# CANBed_FD.net
KiCad netlist of a schematic drawn in EAGLE
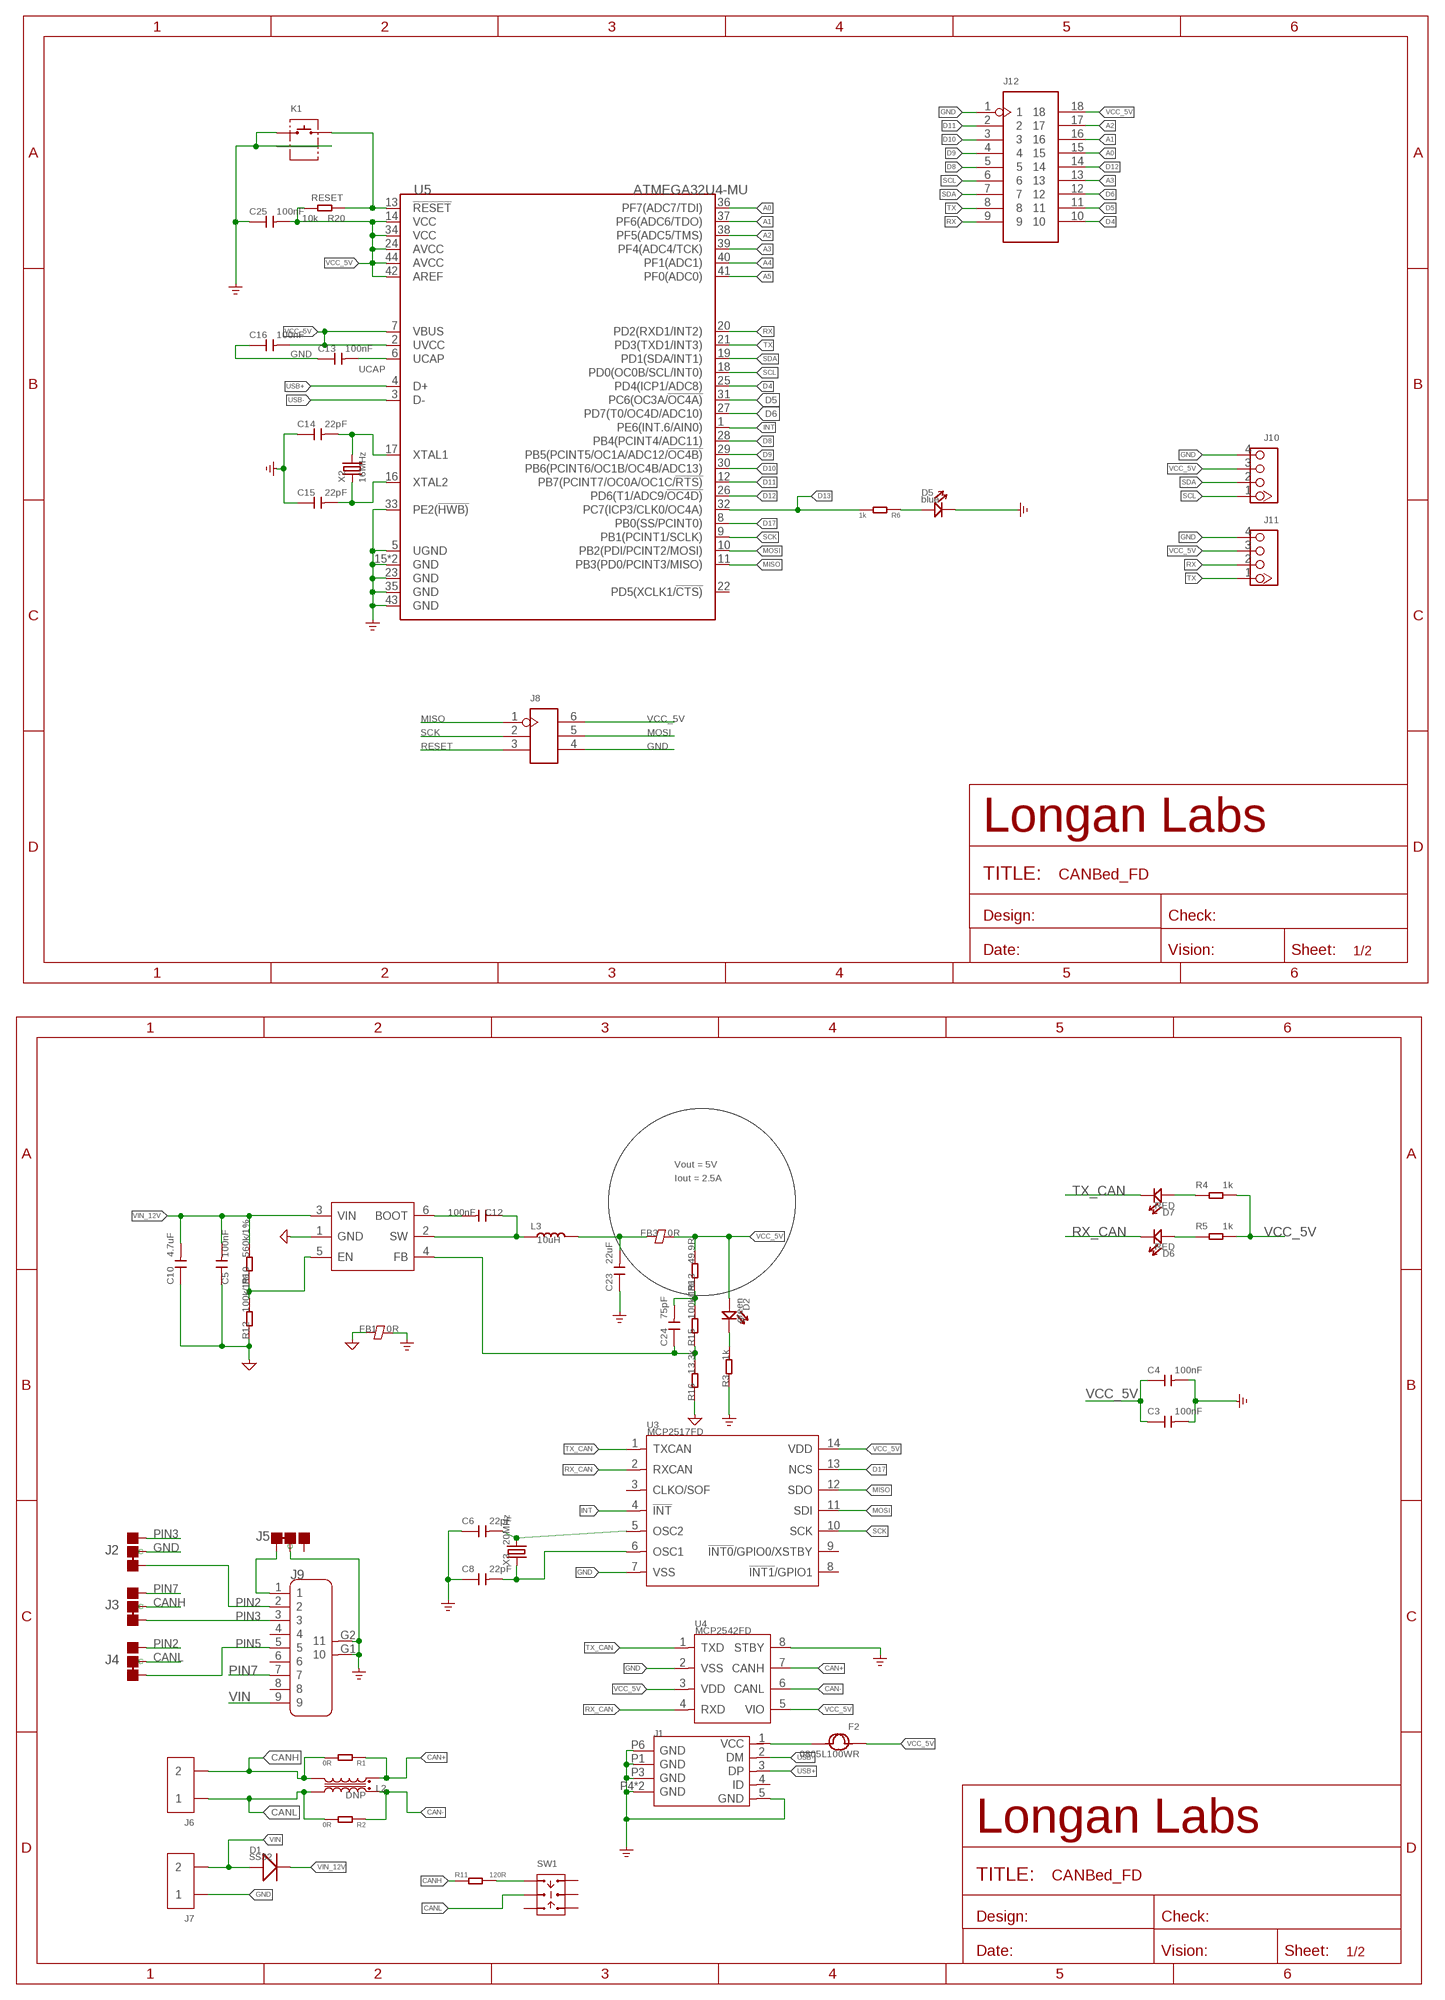
[diagram p0: schematic, sheet 1]

(export (version "E")
  (design (tool "Eeschema 10.0.6"))
  (components
    (comp (ref "C3")
      (value "100nF")
      (footprint "eagle-import:C0603")
      (libsource (lib "eagle-import") (part "CAP-0603"))
    )
    (comp (ref "C4")
      (value "100nF")
      (footprint "eagle-import:C0603")
      (libsource (lib "eagle-import") (part "CAP-0603"))
    )
    (comp (ref "C5")
      (value "100nF")
      (footprint "eagle-import:C0603")
      (libsource (lib "eagle-import") (part "CAP-0603"))
    )
    (comp (ref "C6")
      (value "22pF")
      (footprint "eagle-import:C0603")
      (libsource (lib "eagle-import") (part "CAP-0603"))
    )
    (comp (ref "C8")
      (value "22pF")
      (footprint "eagle-import:C0603")
      (libsource (lib "eagle-import") (part "CAP-0603"))
    )
    (comp (ref "C10")
      (value "4.7uF")
      (footprint "eagle-import:C1206")
      (libsource (lib "eagle-import") (part "CAP-1206"))
    )
    (comp (ref "C12")
      (value "100nF")
      (footprint "eagle-import:C0603")
      (libsource (lib "eagle-import") (part "CAP-0603"))
    )
    (comp (ref "C13")
      (value "100nF")
      (footprint "eagle-import:C0603")
      (libsource (lib "eagle-import") (part "CAP-0603"))
    )
    (comp (ref "C14")
      (value "22pF")
      (footprint "eagle-import:C0603")
      (libsource (lib "eagle-import") (part "CAP-0603"))
    )
    (comp (ref "C15")
      (value "22pF")
      (footprint "eagle-import:C0603")
      (libsource (lib "eagle-import") (part "CAP-0603"))
    )
    (comp (ref "C16")
      (value "100nF")
      (footprint "eagle-import:C0603")
      (libsource (lib "eagle-import") (part "CAP-0603"))
    )
    (comp (ref "C23")
      (value "22uF")
      (footprint "eagle-import:C1206")
      (libsource (lib "eagle-import") (part "CAP-1206"))
    )
    (comp (ref "C24")
      (value "75pF")
      (footprint "eagle-import:C0603")
      (libsource (lib "eagle-import") (part "CAP-0603"))
    )
    (comp (ref "C25")
      (value "100nF")
      (footprint "eagle-import:C0603")
      (libsource (lib "eagle-import") (part "CAP-0603"))
    )
    (comp (ref "D1")
      (value "SS32")
      (footprint "eagle-import:DO-214AC")
      (libsource (lib "eagle-import") (part "DIODE'SMA'"))
    )
    (comp (ref "D2")
      (value "green")
      (footprint "eagle-import:LED-0603")
      (libsource (lib "eagle-import") (part "LED'0603'"))
    )
    (comp (ref "D5")
      (value "blue")
      (footprint "eagle-import:LED-0603")
      (libsource (lib "eagle-import") (part "LED'0603'"))
    )
    (comp (ref "D6")
      (value "RED")
      (footprint "eagle-import:LED-0603")
      (libsource (lib "eagle-import") (part "LED'0603'"))
    )
    (comp (ref "D7")
      (value "RED")
      (footprint "eagle-import:LED-0603")
      (libsource (lib "eagle-import") (part "LED'0603'"))
    )
    (comp (ref "F2")
      (value "0805L100WR")
      (footprint "eagle-import:F0805")
      (libsource (lib "eagle-import") (part "FUSE0805"))
    )
    (comp (ref "FB1")
      (value "0R")
      (footprint "eagle-import:F0805")
      (libsource (lib "eagle-import") (part "FERRITE-BEAD-0805"))
    )
    (comp (ref "FB3")
      (value "0R")
      (footprint "eagle-import:F0805")
      (libsource (lib "eagle-import") (part "FERRITE-BEAD-0805"))
    )
    (comp (ref "J1")
      (value "MICRO-USB5+4P-320010050")
      (footprint "eagle-import:MICRO-USB5+5P-SMD-0.65-7.2X5.06MM")
      (libsource (lib "eagle-import") (part "MICRO-USB5+4P-320010050"))
    )
    (comp (ref "J2")
      (value "JUMPER-3P-SHORT")
      (footprint "eagle-import:3P-SMD-SHORT")
      (libsource (lib "eagle-import") (part "JUMPER-3P-SHORT"))
    )
    (comp (ref "J3")
      (value "JUMPER-3P-SHORT")
      (footprint "eagle-import:3P-SMD-SHORT")
      (libsource (lib "eagle-import") (part "JUMPER-3P-SHORT"))
    )
    (comp (ref "J4")
      (value "JUMPER-3P-SHORT")
      (footprint "eagle-import:3P-SMD-SHORT")
      (libsource (lib "eagle-import") (part "JUMPER-3P-SHORT"))
    )
    (comp (ref "J5")
      (value "JUMPER-3P-SHORT")
      (footprint "eagle-import:3P-SMD-SHORT")
      (libsource (lib "eagle-import") (part "JUMPER-3P-SHORT"))
    )
    (comp (ref "J6")
      (value "SCREW-TERMINAL-2P'5.08'")
      (footprint "eagle-import:H2-5.0-10.5X8.0MM")
      (libsource (lib "eagle-import") (part "SCREW-TERMINAL-2P'5.08'"))
    )
    (comp (ref "J7")
      (value "SCREW-TERMINAL-2P'5.08'")
      (footprint "eagle-import:H2-5.0-10.5X8.0MM")
      (libsource (lib "eagle-import") (part "SCREW-TERMINAL-2P'5.08'"))
    )
    (comp (ref "J8")
      (value "HEADER-2X3P-2.54")
      (footprint "eagle-import:H2X3-2.54")
      (libsource (lib "eagle-import") (part "HEADER-2X3P-2.54"))
    )
    (comp (ref "J9")
      (value "DB9'MEAL'")
      (footprint "eagle-import:DB9-MEAL")
      (libsource (lib "eagle-import") (part "DB9'MEAL'"))
    )
    (comp (ref "J10")
      (value "320110033")
      (footprint "eagle-import:HW4-2.0")
      (libsource (lib "eagle-import") (part "GROVE-CONNECTOR-DIP-2.0"))
    )
    (comp (ref "J11")
      (value "320110033")
      (footprint "eagle-import:HW4-2.0")
      (libsource (lib "eagle-import") (part "GROVE-CONNECTOR-DIP-2.0"))
    )
    (comp (ref "J12")
      (value "HEADER-2X9P-2.54")
      (footprint "eagle-import:H2X9-2.54")
      (libsource (lib "eagle-import") (part "HEADER-2X9P-2.54"))
    )
    (comp (ref "K1")
      (value "BUTTON-2+2P")
      (footprint "eagle-import:SW2+2P-7.7X2.75X3.95MM")
      (libsource (lib "eagle-import") (part "BUTTON-2+2P"))
    )
    (comp (ref "L2")
      (value "DNP")
      (footprint "eagle-import:INT4-0.85-2X1.25X1.2MM")
      (libsource (lib "eagle-import") (part "INDUCTOR-COMMON-MODE-SRF2012-900YA"))
    )
    (comp (ref "L3")
      (value "10uH")
      (footprint "eagle-import:INT2-SMD-6.6X7.1X3MM")
      (libsource (lib "eagle-import") (part "INDUCTOR-6.6X7.1"))
    )
    (comp (ref "R1")
      (value "0R")
      (footprint "eagle-import:R0603")
      (libsource (lib "eagle-import") (part "RES-0603"))
    )
    (comp (ref "R2")
      (value "0R")
      (footprint "eagle-import:R0603")
      (libsource (lib "eagle-import") (part "RES-0603"))
    )
    (comp (ref "R3")
      (value "1k")
      (footprint "eagle-import:R0603")
      (libsource (lib "eagle-import") (part "RES-0603"))
    )
    (comp (ref "R4")
      (value "1k")
      (footprint "eagle-import:R0603")
      (libsource (lib "eagle-import") (part "RES-0603"))
    )
    (comp (ref "R5")
      (value "1k")
      (footprint "eagle-import:R0603")
      (libsource (lib "eagle-import") (part "RES-0603"))
    )
    (comp (ref "R6")
      (value "1k")
      (footprint "eagle-import:R0603")
      (libsource (lib "eagle-import") (part "RES-0603"))
    )
    (comp (ref "R10")
      (value "560k/1%")
      (footprint "eagle-import:R0603")
      (libsource (lib "eagle-import") (part "RES-0603"))
    )
    (comp (ref "R11")
      (value "120R")
      (footprint "eagle-import:R0603")
      (libsource (lib "eagle-import") (part "RES-0603"))
    )
    (comp (ref "R12")
      (value "100k/1%")
      (footprint "eagle-import:R0603")
      (libsource (lib "eagle-import") (part "RES-0603"))
    )
    (comp (ref "R13")
      (value "49.9R")
      (footprint "eagle-import:R0603")
      (libsource (lib "eagle-import") (part "RES-0603"))
    )
    (comp (ref "R15")
      (value "100k/1%")
      (footprint "eagle-import:R0603")
      (libsource (lib "eagle-import") (part "RES-0603"))
    )
    (comp (ref "R16")
      (value "13.3k")
      (footprint "eagle-import:R0603")
      (libsource (lib "eagle-import") (part "RES-0603"))
    )
    (comp (ref "R20")
      (value "10k")
      (footprint "eagle-import:R0603")
      (libsource (lib "eagle-import") (part "RES-0603"))
    )
    (comp (ref "SW1")
      (value "SWITCH-2CH-6P-311010004")
      (footprint "eagle-import:SW6-2.54-9.0X3.5X3.2+2.0MM")
      (libsource (lib "eagle-import") (part "SWITCH-2CH-6P-311010004"))
    )
    (comp (ref "U1")
      (value "PMIC-TPS54302")
      (footprint "eagle-import:SOT-23-6")
      (libsource (lib "eagle-import") (part "PMIC-TPS54302"))
    )
    (comp (ref "U3")
      (value "MCP2517FD")
      (footprint "eagle-import:SOIC14-1.27-8.6X3.9MM")
      (libsource (lib "eagle-import") (part "CONTROLLER-MCP2517FD"))
    )
    (comp (ref "U4")
      (value "MCP2542FD")
      (footprint "eagle-import:SOIC8-1.27-5X4MM")
      (libsource (lib "eagle-import") (part "TRANSCEIVER-MCP2542"))
    )
    (comp (ref "U5")
      (value "ATMEGA32U4-MU")
      (footprint "eagle-import:QFN44")
      (libsource (lib "eagle-import") (part "ATMEGA32U4-MU"))
    )
    (comp (ref "X2")
      (value "16MHz")
      (footprint "eagle-import:HC49US")
      (libsource (lib "eagle-import") (part "CRYSTAL-2P'HC49US'"))
    )
    (comp (ref "X3")
      (value "20MHz")
      (footprint "eagle-import:HC49US")
      (libsource (lib "eagle-import") (part "CRYSTAL-2P'HC49US'"))
    )
  )
  (nets
    (net (code "1") (name "A0") (class "Default")
      (node (ref "J12") (pin "15") (pinfunction "15_15") (pintype "bidirectional"))
      (node (ref "U5") (pin "36") (pinfunction "PF7(ADC7/TDI)_36") (pintype "bidirectional"))
    )
    (net (code "2") (name "A1") (class "Default")
      (node (ref "J12") (pin "16") (pinfunction "16_16") (pintype "bidirectional"))
      (node (ref "U5") (pin "37") (pinfunction "PF6(ADC6/TDO)_37") (pintype "bidirectional"))
    )
    (net (code "3") (name "A2") (class "Default")
      (node (ref "J12") (pin "17") (pinfunction "17_17") (pintype "bidirectional"))
      (node (ref "U5") (pin "38") (pinfunction "PF5(ADC5/TMS)_38") (pintype "bidirectional"))
    )
    (net (code "4") (name "A3") (class "Default")
      (node (ref "J12") (pin "13") (pinfunction "13_13") (pintype "bidirectional"))
      (node (ref "U5") (pin "39") (pinfunction "PF4(ADC4/TCK)_39") (pintype "bidirectional"))
    )
    (net (code "5") (name "A4") (class "Default")
      (node (ref "U5") (pin "40") (pinfunction "PF1(ADC1)_40") (pintype "bidirectional"))
    )
    (net (code "6") (name "A5") (class "Default")
      (node (ref "U5") (pin "41") (pinfunction "PF0(ADC0)_41") (pintype "bidirectional"))
    )
    (net (code "7") (name "AGND") (class "Default")
      (node (ref "C10") (pin "1") (pinfunction "1_1") (pintype "passive"))
      (node (ref "C5") (pin "1") (pinfunction "1_1") (pintype "passive"))
      (node (ref "FB1") (pin "1") (pinfunction "1_1") (pintype "bidirectional"))
      (node (ref "R12") (pin "1") (pinfunction "1_1") (pintype "passive"))
      (node (ref "R16") (pin "1") (pinfunction "1_1") (pintype "passive"))
      (node (ref "U1") (pin "1") (pinfunction "GND_1") (pintype "bidirectional"))
    )
    (net (code "8") (name "CAN+") (class "Default")
      (node (ref "L2") (pin "4") (pinfunction "4_4") (pintype "bidirectional"))
      (node (ref "R1") (pin "1") (pinfunction "1_1") (pintype "passive"))
      (node (ref "U4") (pin "7") (pinfunction "CANH_7") (pintype "bidirectional"))
    )
    (net (code "9") (name "CAN-") (class "Default")
      (node (ref "L2") (pin "1") (pinfunction "1_1") (pintype "bidirectional"))
      (node (ref "R2") (pin "1") (pinfunction "1_1") (pintype "passive"))
      (node (ref "U4") (pin "6") (pinfunction "CANL_6") (pintype "bidirectional"))
    )
    (net (code "10") (name "CANH") (class "Default")
      (node (ref "J3") (pin "MM") (pinfunction "C_MM") (pintype "bidirectional"))
      (node (ref "J6") (pin "2") (pinfunction "2_2") (pintype "bidirectional"))
      (node (ref "L2") (pin "3") (pinfunction "3_3") (pintype "bidirectional"))
      (node (ref "R1") (pin "2") (pinfunction "2_2") (pintype "passive"))
      (node (ref "R11") (pin "1") (pinfunction "1_1") (pintype "passive"))
    )
    (net (code "11") (name "CANL") (class "Default")
      (node (ref "J4") (pin "MM") (pinfunction "C_MM") (pintype "bidirectional"))
      (node (ref "J6") (pin "1") (pinfunction "1_1") (pintype "bidirectional"))
      (node (ref "L2") (pin "2") (pinfunction "2_2") (pintype "bidirectional"))
      (node (ref "R2") (pin "2") (pinfunction "2_2") (pintype "passive"))
      (node (ref "SW1") (pin "COM1") (pinfunction "COM1_COM1") (pintype "bidirectional"))
    )
    (net (code "12") (name "D4") (class "Default")
      (node (ref "J12") (pin "10") (pinfunction "10_10") (pintype "bidirectional"))
      (node (ref "U5") (pin "25") (pinfunction "PD4(ICP1/ADC8)_25") (pintype "bidirectional"))
    )
    (net (code "13") (name "D5") (class "Default")
      (node (ref "J12") (pin "11") (pinfunction "11_11") (pintype "bidirectional"))
      (node (ref "U5") (pin "31") (pinfunction "PC6(OC3A/~{OC4A})_31") (pintype "bidirectional"))
    )
    (net (code "14") (name "D6") (class "Default")
      (node (ref "J12") (pin "12") (pinfunction "12_12") (pintype "bidirectional"))
      (node (ref "U5") (pin "27") (pinfunction "PD7(T0/OC4D/ADC10)_27") (pintype "bidirectional"))
    )
    (net (code "15") (name "D8") (class "Default")
      (node (ref "J12") (pin "5") (pinfunction "5_5") (pintype "bidirectional"))
      (node (ref "U5") (pin "28") (pinfunction "PB4(PCINT4/ADC11)_28") (pintype "bidirectional"))
    )
    (net (code "16") (name "D9") (class "Default")
      (node (ref "J12") (pin "4") (pinfunction "4_4") (pintype "bidirectional"))
      (node (ref "U5") (pin "29") (pinfunction "PB5(PCINT5/OC1A/ADC12/~{OC4B})_29") (pintype "bidirectional"))
    )
    (net (code "17") (name "D10") (class "Default")
      (node (ref "J12") (pin "3") (pinfunction "3_3") (pintype "bidirectional"))
      (node (ref "U5") (pin "30") (pinfunction "PB6(PCINT6/OC1B/OC4B/ADC13)_30") (pintype "bidirectional"))
    )
    (net (code "18") (name "D11") (class "Default")
      (node (ref "J12") (pin "2") (pinfunction "2_2") (pintype "bidirectional"))
      (node (ref "U5") (pin "12") (pinfunction "PB7(PCINT7/OC0A/OC1C/~{RTS})_12") (pintype "bidirectional"))
    )
    (net (code "19") (name "D12") (class "Default")
      (node (ref "J12") (pin "14") (pinfunction "14_14") (pintype "bidirectional"))
      (node (ref "U5") (pin "26") (pinfunction "PD6(T1/ADC9/~{OC4D})_26") (pintype "bidirectional"))
    )
    (net (code "20") (name "D13") (class "Default")
      (node (ref "R6") (pin "2") (pinfunction "2_2") (pintype "passive"))
      (node (ref "U5") (pin "32") (pinfunction "PC7(ICP3/CLK0/OC4A)_32") (pintype "bidirectional"))
    )
    (net (code "21") (name "D17") (class "Default")
      (node (ref "U3") (pin "13") (pinfunction "NCS_13") (pintype "bidirectional"))
      (node (ref "U5") (pin "8") (pinfunction "PB0(SS/PCINT0)_8") (pintype "bidirectional"))
    )
    (net (code "22") (name "GND") (class "Default")
      (node (ref "C13") (pin "1") (pinfunction "1_1") (pintype "passive"))
      (node (ref "C14") (pin "1") (pinfunction "1_1") (pintype "passive"))
      (node (ref "C15") (pin "1") (pinfunction "1_1") (pintype "passive"))
      (node (ref "C16") (pin "1") (pinfunction "1_1") (pintype "passive"))
      (node (ref "C23") (pin "1") (pinfunction "1_1") (pintype "passive"))
      (node (ref "C25") (pin "1") (pinfunction "1_1") (pintype "passive"))
      (node (ref "C3") (pin "2") (pinfunction "2_2") (pintype "passive"))
      (node (ref "C4") (pin "2") (pinfunction "2_2") (pintype "passive"))
      (node (ref "C6") (pin "1") (pinfunction "1_1") (pintype "passive"))
      (node (ref "C8") (pin "1") (pinfunction "1_1") (pintype "passive"))
      (node (ref "D5") (pin "-") (pinfunction "-_-") (pintype "passive"))
      (node (ref "FB1") (pin "2") (pinfunction "2_2") (pintype "bidirectional"))
      (node (ref "J1") (pin "5") (pinfunction "GND_5") (pintype "bidirectional"))
      (node (ref "J1") (pin "P1") (pinfunction "GND_P1") (pintype "bidirectional"))
      (node (ref "J1") (pin "P3") (pinfunction "GND_P3") (pintype "bidirectional"))
      (node (ref "J1") (pin "P4") (pinfunction "GND_P4") (pintype "bidirectional"))
      (node (ref "J1") (pin "P5") (pinfunction "GND_P5") (pintype "bidirectional"))
      (node (ref "J1") (pin "P6") (pinfunction "GND_P6") (pintype "bidirectional"))
      (node (ref "J10") (pin "4") (pinfunction "4_4") (pintype "bidirectional"))
      (node (ref "J11") (pin "4") (pinfunction "4_4") (pintype "bidirectional"))
      (node (ref "J12") (pin "1") (pinfunction "1_1") (pintype "bidirectional"))
      (node (ref "J2") (pin "MM") (pinfunction "C_MM") (pintype "bidirectional"))
      (node (ref "J5") (pin "MM") (pinfunction "C_MM") (pintype "bidirectional"))
      (node (ref "J7") (pin "1") (pinfunction "1_1") (pintype "bidirectional"))
      (node (ref "J8") (pin "4") (pinfunction "4_4") (pintype "bidirectional"))
      (node (ref "J9") (pin "G1") (pinfunction "10_G1") (pintype "bidirectional"))
      (node (ref "J9") (pin "G2") (pinfunction "11_G2") (pintype "bidirectional"))
      (node (ref "K1") (pin "1") (pinfunction "1_1") (pintype "bidirectional"))
      (node (ref "K1") (pin "S1") (pinfunction "S1_S1") (pintype "bidirectional"))
      (node (ref "K1") (pin "S2") (pinfunction "S2_S2") (pintype "bidirectional"))
      (node (ref "R3") (pin "1") (pinfunction "1_1") (pintype "passive"))
      (node (ref "U3") (pin "7") (pinfunction "VSS_7") (pintype "bidirectional"))
      (node (ref "U4") (pin "2") (pinfunction "VSS_2") (pintype "bidirectional"))
      (node (ref "U4") (pin "8") (pinfunction "STBY_8") (pintype "bidirectional"))
      (node (ref "U5") (pin "15") (pinfunction "GND_15") (pintype "bidirectional"))
      (node (ref "U5") (pin "23") (pinfunction "GND_23") (pintype "bidirectional"))
      (node (ref "U5") (pin "33") (pinfunction "PE2(~{HWB})_33") (pintype "bidirectional"))
      (node (ref "U5") (pin "35") (pinfunction "GND_35") (pintype "bidirectional"))
      (node (ref "U5") (pin "43") (pinfunction "GND_43") (pintype "bidirectional"))
      (node (ref "U5") (pin "5") (pinfunction "UGND_5") (pintype "bidirectional"))
      (node (ref "U5") (pin "TAB") (pinfunction "GND_TAB") (pintype "bidirectional"))
    )
    (net (code "23") (name "INT") (class "Default")
      (node (ref "U3") (pin "4") (pinfunction "~{INT}_4") (pintype "bidirectional"))
      (node (ref "U5") (pin "1") (pinfunction "PE6(INT.6/AIN0)_1") (pintype "bidirectional"))
    )
    (net (code "24") (name "MISO") (class "Default")
      (node (ref "J8") (pin "1") (pinfunction "1_1") (pintype "bidirectional"))
      (node (ref "U3") (pin "12") (pinfunction "SDO_12") (pintype "bidirectional"))
      (node (ref "U5") (pin "11") (pinfunction "PB3(PD0/PCINT3/MISO)_11") (pintype "bidirectional"))
    )
    (net (code "25") (name "MOSI") (class "Default")
      (node (ref "J8") (pin "5") (pinfunction "5_5") (pintype "bidirectional"))
      (node (ref "U3") (pin "11") (pinfunction "SDI_11") (pintype "bidirectional"))
      (node (ref "U5") (pin "10") (pinfunction "PB2(PDI/PCINT2/MOSI)_10") (pintype "bidirectional"))
    )
    (net (code "26") (name "Net-(C23-Pad2)") (class "Default")
      (node (ref "C23") (pin "2") (pinfunction "2_2") (pintype "passive"))
      (node (ref "FB3") (pin "1") (pinfunction "1_1") (pintype "bidirectional"))
      (node (ref "L3") (pin "2") (pinfunction "2_2") (pintype "passive"))
    )
    (net (code "27") (name "Net-(C24-Pad2)") (class "Default")
      (node (ref "C24") (pin "2") (pinfunction "2_2") (pintype "passive"))
      (node (ref "R13") (pin "1") (pinfunction "1_1") (pintype "passive"))
      (node (ref "R15") (pin "2") (pinfunction "2_2") (pintype "passive"))
    )
    (net (code "28") (name "Net-(D2-Pad-)") (class "Default")
      (node (ref "D2") (pin "-") (pinfunction "-_-") (pintype "passive"))
      (node (ref "R3") (pin "2") (pinfunction "2_2") (pintype "passive"))
    )
    (net (code "29") (name "Net-(D5-Pad+)") (class "Default")
      (node (ref "D5") (pin "+") (pinfunction "+_+") (pintype "passive"))
      (node (ref "R6") (pin "1") (pinfunction "1_1") (pintype "passive"))
    )
    (net (code "30") (name "Net-(D6-Pad+)") (class "Default")
      (node (ref "D6") (pin "+") (pinfunction "+_+") (pintype "passive"))
      (node (ref "R5") (pin "1") (pinfunction "1_1") (pintype "passive"))
    )
    (net (code "31") (name "Net-(D7-Pad+)") (class "Default")
      (node (ref "D7") (pin "+") (pinfunction "+_+") (pintype "passive"))
      (node (ref "R4") (pin "1") (pinfunction "1_1") (pintype "passive"))
    )
    (net (code "32") (name "Net-(J1-VCC)") (class "Default")
      (node (ref "F2") (pin "2") (pinfunction "2_2") (pintype "bidirectional"))
      (node (ref "J1") (pin "1") (pinfunction "VCC_1") (pintype "bidirectional"))
    )
    (net (code "33") (name "Net-(J5-L)") (class "Default")
      (node (ref "J5") (pin "11") (pinfunction "L_11") (pintype "bidirectional"))
      (node (ref "J9") (pin "1") (pinfunction "1_1") (pintype "bidirectional"))
    )
    (net (code "34") (name "Net-(R11-Pad2)") (class "Default")
      (node (ref "R11") (pin "2") (pinfunction "2_2") (pintype "passive"))
      (node (ref "SW1") (pin "CH1A") (pinfunction "CH1A_CH1A") (pintype "bidirectional"))
    )
    (net (code "35") (name "Net-(U1-BOOT)") (class "Default")
      (node (ref "C12") (pin "2") (pinfunction "2_2") (pintype "passive"))
      (node (ref "U1") (pin "6") (pinfunction "BOOT_6") (pintype "bidirectional"))
    )
    (net (code "36") (name "Net-(U1-EN)") (class "Default")
      (node (ref "R10") (pin "1") (pinfunction "1_1") (pintype "passive"))
      (node (ref "R12") (pin "2") (pinfunction "2_2") (pintype "passive"))
      (node (ref "U1") (pin "5") (pinfunction "EN_5") (pintype "bidirectional"))
    )
    (net (code "37") (name "Net-(U1-FB)") (class "Default")
      (node (ref "C24") (pin "1") (pinfunction "1_1") (pintype "passive"))
      (node (ref "R15") (pin "1") (pinfunction "1_1") (pintype "passive"))
      (node (ref "R16") (pin "2") (pinfunction "2_2") (pintype "passive"))
      (node (ref "U1") (pin "4") (pinfunction "FB_4") (pintype "bidirectional"))
    )
    (net (code "38") (name "Net-(U1-SW)") (class "Default")
      (node (ref "C12") (pin "1") (pinfunction "1_1") (pintype "passive"))
      (node (ref "L3") (pin "1") (pinfunction "1_1") (pintype "passive"))
      (node (ref "U1") (pin "2") (pinfunction "SW_2") (pintype "bidirectional"))
    )
    (net (code "39") (name "Net-(U3-OSC1)") (class "Default")
      (node (ref "C8") (pin "2") (pinfunction "2_2") (pintype "passive"))
      (node (ref "U3") (pin "6") (pinfunction "OSC1_6") (pintype "bidirectional"))
      (node (ref "X3") (pin "1") (pinfunction "1_1") (pintype "passive"))
    )
    (net (code "40") (name "Net-(U3-OSC2)") (class "Default")
      (node (ref "C6") (pin "2") (pinfunction "2_2") (pintype "passive"))
      (node (ref "U3") (pin "5") (pinfunction "OSC2_5") (pintype "bidirectional"))
      (node (ref "X3") (pin "2") (pinfunction "2_2") (pintype "passive"))
    )
    (net (code "41") (name "Net-(U5-XTAL1)") (class "Default")
      (node (ref "C14") (pin "2") (pinfunction "2_2") (pintype "passive"))
      (node (ref "U5") (pin "17") (pinfunction "XTAL1_17") (pintype "bidirectional"))
      (node (ref "X2") (pin "2") (pinfunction "2_2") (pintype "passive"))
    )
    (net (code "42") (name "Net-(U5-XTAL2)") (class "Default")
      (node (ref "C15") (pin "2") (pinfunction "2_2") (pintype "passive"))
      (node (ref "U5") (pin "16") (pinfunction "XTAL2_16") (pintype "bidirectional"))
      (node (ref "X2") (pin "1") (pinfunction "1_1") (pintype "passive"))
    )
    (net (code "43") (name "PIN2") (class "Default")
      (node (ref "J2") (pin "11") (pinfunction "L_11") (pintype "bidirectional"))
      (node (ref "J4") (pin "00") (pinfunction "R_00") (pintype "bidirectional"))
      (node (ref "J9") (pin "2") (pinfunction "2_2") (pintype "bidirectional"))
    )
    (net (code "44") (name "PIN3") (class "Default")
      (node (ref "J2") (pin "00") (pinfunction "R_00") (pintype "bidirectional"))
      (node (ref "J3") (pin "11") (pinfunction "L_11") (pintype "bidirectional"))
      (node (ref "J9") (pin "3") (pinfunction "3_3") (pintype "bidirectional"))
    )
    (net (code "45") (name "PIN5") (class "Default")
      (node (ref "J4") (pin "11") (pinfunction "L_11") (pintype "bidirectional"))
      (node (ref "J9") (pin "5") (pinfunction "5_5") (pintype "bidirectional"))
    )
    (net (code "46") (name "PIN7") (class "Default")
      (node (ref "J3") (pin "00") (pinfunction "R_00") (pintype "bidirectional"))
      (node (ref "J9") (pin "7") (pinfunction "7_7") (pintype "bidirectional"))
    )
    (net (code "47") (name "RESET") (class "Default")
      (node (ref "J8") (pin "3") (pinfunction "3_3") (pintype "bidirectional"))
      (node (ref "K1") (pin "2") (pinfunction "2_2") (pintype "bidirectional"))
      (node (ref "R20") (pin "1") (pinfunction "1_1") (pintype "passive"))
      (node (ref "U5") (pin "13") (pinfunction "~{RESET}_13") (pintype "bidirectional"))
    )
    (net (code "48") (name "RX") (class "Default")
      (node (ref "J11") (pin "2") (pinfunction "2_2") (pintype "bidirectional"))
      (node (ref "J12") (pin "9") (pinfunction "9_9") (pintype "bidirectional"))
      (node (ref "U5") (pin "20") (pinfunction "PD2(RXD1/INT2)_20") (pintype "bidirectional"))
    )
    (net (code "49") (name "RX_CAN") (class "Default")
      (node (ref "D6") (pin "-") (pinfunction "-_-") (pintype "passive"))
      (node (ref "U3") (pin "2") (pinfunction "RXCAN_2") (pintype "bidirectional"))
      (node (ref "U4") (pin "4") (pinfunction "RXD_4") (pintype "bidirectional"))
    )
    (net (code "50") (name "SCK") (class "Default")
      (node (ref "J8") (pin "2") (pinfunction "2_2") (pintype "bidirectional"))
      (node (ref "U3") (pin "10") (pinfunction "SCK_10") (pintype "bidirectional"))
      (node (ref "U5") (pin "9") (pinfunction "PB1(PCINT1/SCLK)_9") (pintype "bidirectional"))
    )
    (net (code "51") (name "SCL") (class "Default")
      (node (ref "J10") (pin "1") (pinfunction "1_1") (pintype "bidirectional"))
      (node (ref "J12") (pin "6") (pinfunction "6_6") (pintype "bidirectional"))
      (node (ref "U5") (pin "18") (pinfunction "PD0(OC0B/SCL/INT0)_18") (pintype "bidirectional"))
    )
    (net (code "52") (name "SDA") (class "Default")
      (node (ref "J10") (pin "2") (pinfunction "2_2") (pintype "bidirectional"))
      (node (ref "J12") (pin "7") (pinfunction "7_7") (pintype "bidirectional"))
      (node (ref "U5") (pin "19") (pinfunction "PD1(SDA/INT1)_19") (pintype "bidirectional"))
    )
    (net (code "53") (name "TX") (class "Default")
      (node (ref "J11") (pin "1") (pinfunction "1_1") (pintype "bidirectional"))
      (node (ref "J12") (pin "8") (pinfunction "8_8") (pintype "bidirectional"))
      (node (ref "U5") (pin "21") (pinfunction "PD3(TXD1/INT3)_21") (pintype "bidirectional"))
    )
    (net (code "54") (name "TX_CAN") (class "Default")
      (node (ref "D7") (pin "-") (pinfunction "-_-") (pintype "passive"))
      (node (ref "U3") (pin "1") (pinfunction "TXCAN_1") (pintype "bidirectional"))
      (node (ref "U4") (pin "1") (pinfunction "TXD_1") (pintype "bidirectional"))
    )
    (net (code "55") (name "UCAP") (class "Default")
      (node (ref "C13") (pin "2") (pinfunction "2_2") (pintype "passive"))
      (node (ref "U5") (pin "6") (pinfunction "UCAP_6") (pintype "bidirectional"))
    )
    (net (code "56") (name "USB+") (class "Default")
      (node (ref "J1") (pin "3") (pinfunction "DP_3") (pintype "bidirectional"))
      (node (ref "U5") (pin "4") (pinfunction "D+_4") (pintype "bidirectional"))
    )
    (net (code "57") (name "USB-") (class "Default")
      (node (ref "J1") (pin "2") (pinfunction "DM_2") (pintype "bidirectional"))
      (node (ref "U5") (pin "3") (pinfunction "D-_3") (pintype "bidirectional"))
    )
    (net (code "58") (name "VCC_5V") (class "Default")
      (node (ref "C16") (pin "2") (pinfunction "2_2") (pintype "passive"))
      (node (ref "C25") (pin "2") (pinfunction "2_2") (pintype "passive"))
      (node (ref "C3") (pin "1") (pinfunction "1_1") (pintype "passive"))
      (node (ref "C4") (pin "1") (pinfunction "1_1") (pintype "passive"))
      (node (ref "D2") (pin "+") (pinfunction "+_+") (pintype "passive"))
      (node (ref "F2") (pin "1") (pinfunction "1_1") (pintype "bidirectional"))
      (node (ref "FB3") (pin "2") (pinfunction "2_2") (pintype "bidirectional"))
      (node (ref "J10") (pin "3") (pinfunction "3_3") (pintype "bidirectional"))
      (node (ref "J11") (pin "3") (pinfunction "3_3") (pintype "bidirectional"))
      (node (ref "J12") (pin "18") (pinfunction "18_18") (pintype "bidirectional"))
      (node (ref "J8") (pin "6") (pinfunction "6_6") (pintype "bidirectional"))
      (node (ref "R13") (pin "2") (pinfunction "2_2") (pintype "passive"))
      (node (ref "R20") (pin "2") (pinfunction "2_2") (pintype "passive"))
      (node (ref "R4") (pin "2") (pinfunction "2_2") (pintype "passive"))
      (node (ref "R5") (pin "2") (pinfunction "2_2") (pintype "passive"))
      (node (ref "U3") (pin "14") (pinfunction "VDD_14") (pintype "bidirectional"))
      (node (ref "U4") (pin "3") (pinfunction "VDD_3") (pintype "bidirectional"))
      (node (ref "U4") (pin "5") (pinfunction "VIO_5") (pintype "bidirectional"))
      (node (ref "U5") (pin "14") (pinfunction "VCC_14") (pintype "bidirectional"))
      (node (ref "U5") (pin "2") (pinfunction "UVCC_2") (pintype "bidirectional"))
      (node (ref "U5") (pin "24") (pinfunction "AVCC_24") (pintype "bidirectional"))
      (node (ref "U5") (pin "34") (pinfunction "VCC_34") (pintype "bidirectional"))
      (node (ref "U5") (pin "42") (pinfunction "AREF_42") (pintype "bidirectional"))
      (node (ref "U5") (pin "44") (pinfunction "AVCC_44") (pintype "bidirectional"))
      (node (ref "U5") (pin "7") (pinfunction "VBUS_7") (pintype "bidirectional"))
    )
    (net (code "59") (name "VIN") (class "Default")
      (node (ref "D1") (pin "1") (pinfunction "+_1") (pintype "passive"))
      (node (ref "J7") (pin "2") (pinfunction "2_2") (pintype "bidirectional"))
      (node (ref "J9") (pin "9") (pinfunction "9_9") (pintype "bidirectional"))
    )
    (net (code "60") (name "VIN_12V") (class "Default")
      (node (ref "C10") (pin "2") (pinfunction "2_2") (pintype "passive"))
      (node (ref "C5") (pin "2") (pinfunction "2_2") (pintype "passive"))
      (node (ref "D1") (pin "2") (pinfunction "-_2") (pintype "passive"))
      (node (ref "R10") (pin "2") (pinfunction "2_2") (pintype "passive"))
      (node (ref "U1") (pin "3") (pinfunction "VIN_3") (pintype "bidirectional"))
    )
    (net (code "61") (name "unconnected-(J1-ID-Pad4)") (class "Default")
      (node (ref "J1") (pin "4") (pinfunction "ID_4") (pintype "bidirectional"))
    )
    (net (code "62") (name "unconnected-(J5-R-Pad00)") (class "Default")
      (node (ref "J5") (pin "00") (pinfunction "R_00") (pintype "bidirectional"))
    )
    (net (code "63") (name "unconnected-(J9-Pad4)") (class "Default")
      (node (ref "J9") (pin "4") (pinfunction "4_4") (pintype "bidirectional"))
    )
    (net (code "64") (name "unconnected-(J9-Pad6)") (class "Default")
      (node (ref "J9") (pin "6") (pinfunction "6_6") (pintype "bidirectional"))
    )
    (net (code "65") (name "unconnected-(J9-Pad8)") (class "Default")
      (node (ref "J9") (pin "8") (pinfunction "8_8") (pintype "bidirectional"))
    )
    (net (code "66") (name "unconnected-(SW1-PadCH1B)") (class "Default")
      (node (ref "SW1") (pin "CH1B") (pinfunction "CH1B_CH1B") (pintype "bidirectional"))
    )
    (net (code "67") (name "unconnected-(SW1-PadCH2A)") (class "Default")
      (node (ref "SW1") (pin "CH2A") (pinfunction "CH2A_CH2A") (pintype "bidirectional"))
    )
    (net (code "68") (name "unconnected-(SW1-PadCH2B)") (class "Default")
      (node (ref "SW1") (pin "CH2B") (pinfunction "CH2B_CH2B") (pintype "bidirectional"))
    )
    (net (code "69") (name "unconnected-(SW1-PadCOM2)") (class "Default")
      (node (ref "SW1") (pin "COM2") (pinfunction "COM2_COM2") (pintype "bidirectional"))
    )
    (net (code "70") (name "unconnected-(U3-CLKO{slash}SOF-Pad3)") (class "Default")
      (node (ref "U3") (pin "3") (pinfunction "CLKO/SOF_3") (pintype "bidirectional"))
    )
    (net (code "71") (name "unconnected-(U3-~{INT0}{slash}GPIO0{slash}XSTBY-Pad9)") (class "Default")
      (node (ref "U3") (pin "9") (pinfunction "~{INT0}/GPIO0/XSTBY_9") (pintype "bidirectional"))
    )
    (net (code "72") (name "unconnected-(U3-~{INT1}{slash}GPIO1-Pad8)") (class "Default")
      (node (ref "U3") (pin "8") (pinfunction "~{INT1}/GPIO1_8") (pintype "bidirectional"))
    )
    (net (code "73") (name "unconnected-(U5-PD5(XCLK1{slash}~{CTS})-Pad22)") (class "Default")
      (node (ref "U5") (pin "22") (pinfunction "PD5(XCLK1/~{CTS})_22") (pintype "bidirectional"))
    )
  )
)
